# Pr_tica-11.net
KiCad netlist of a schematic drawn in EasyEDA
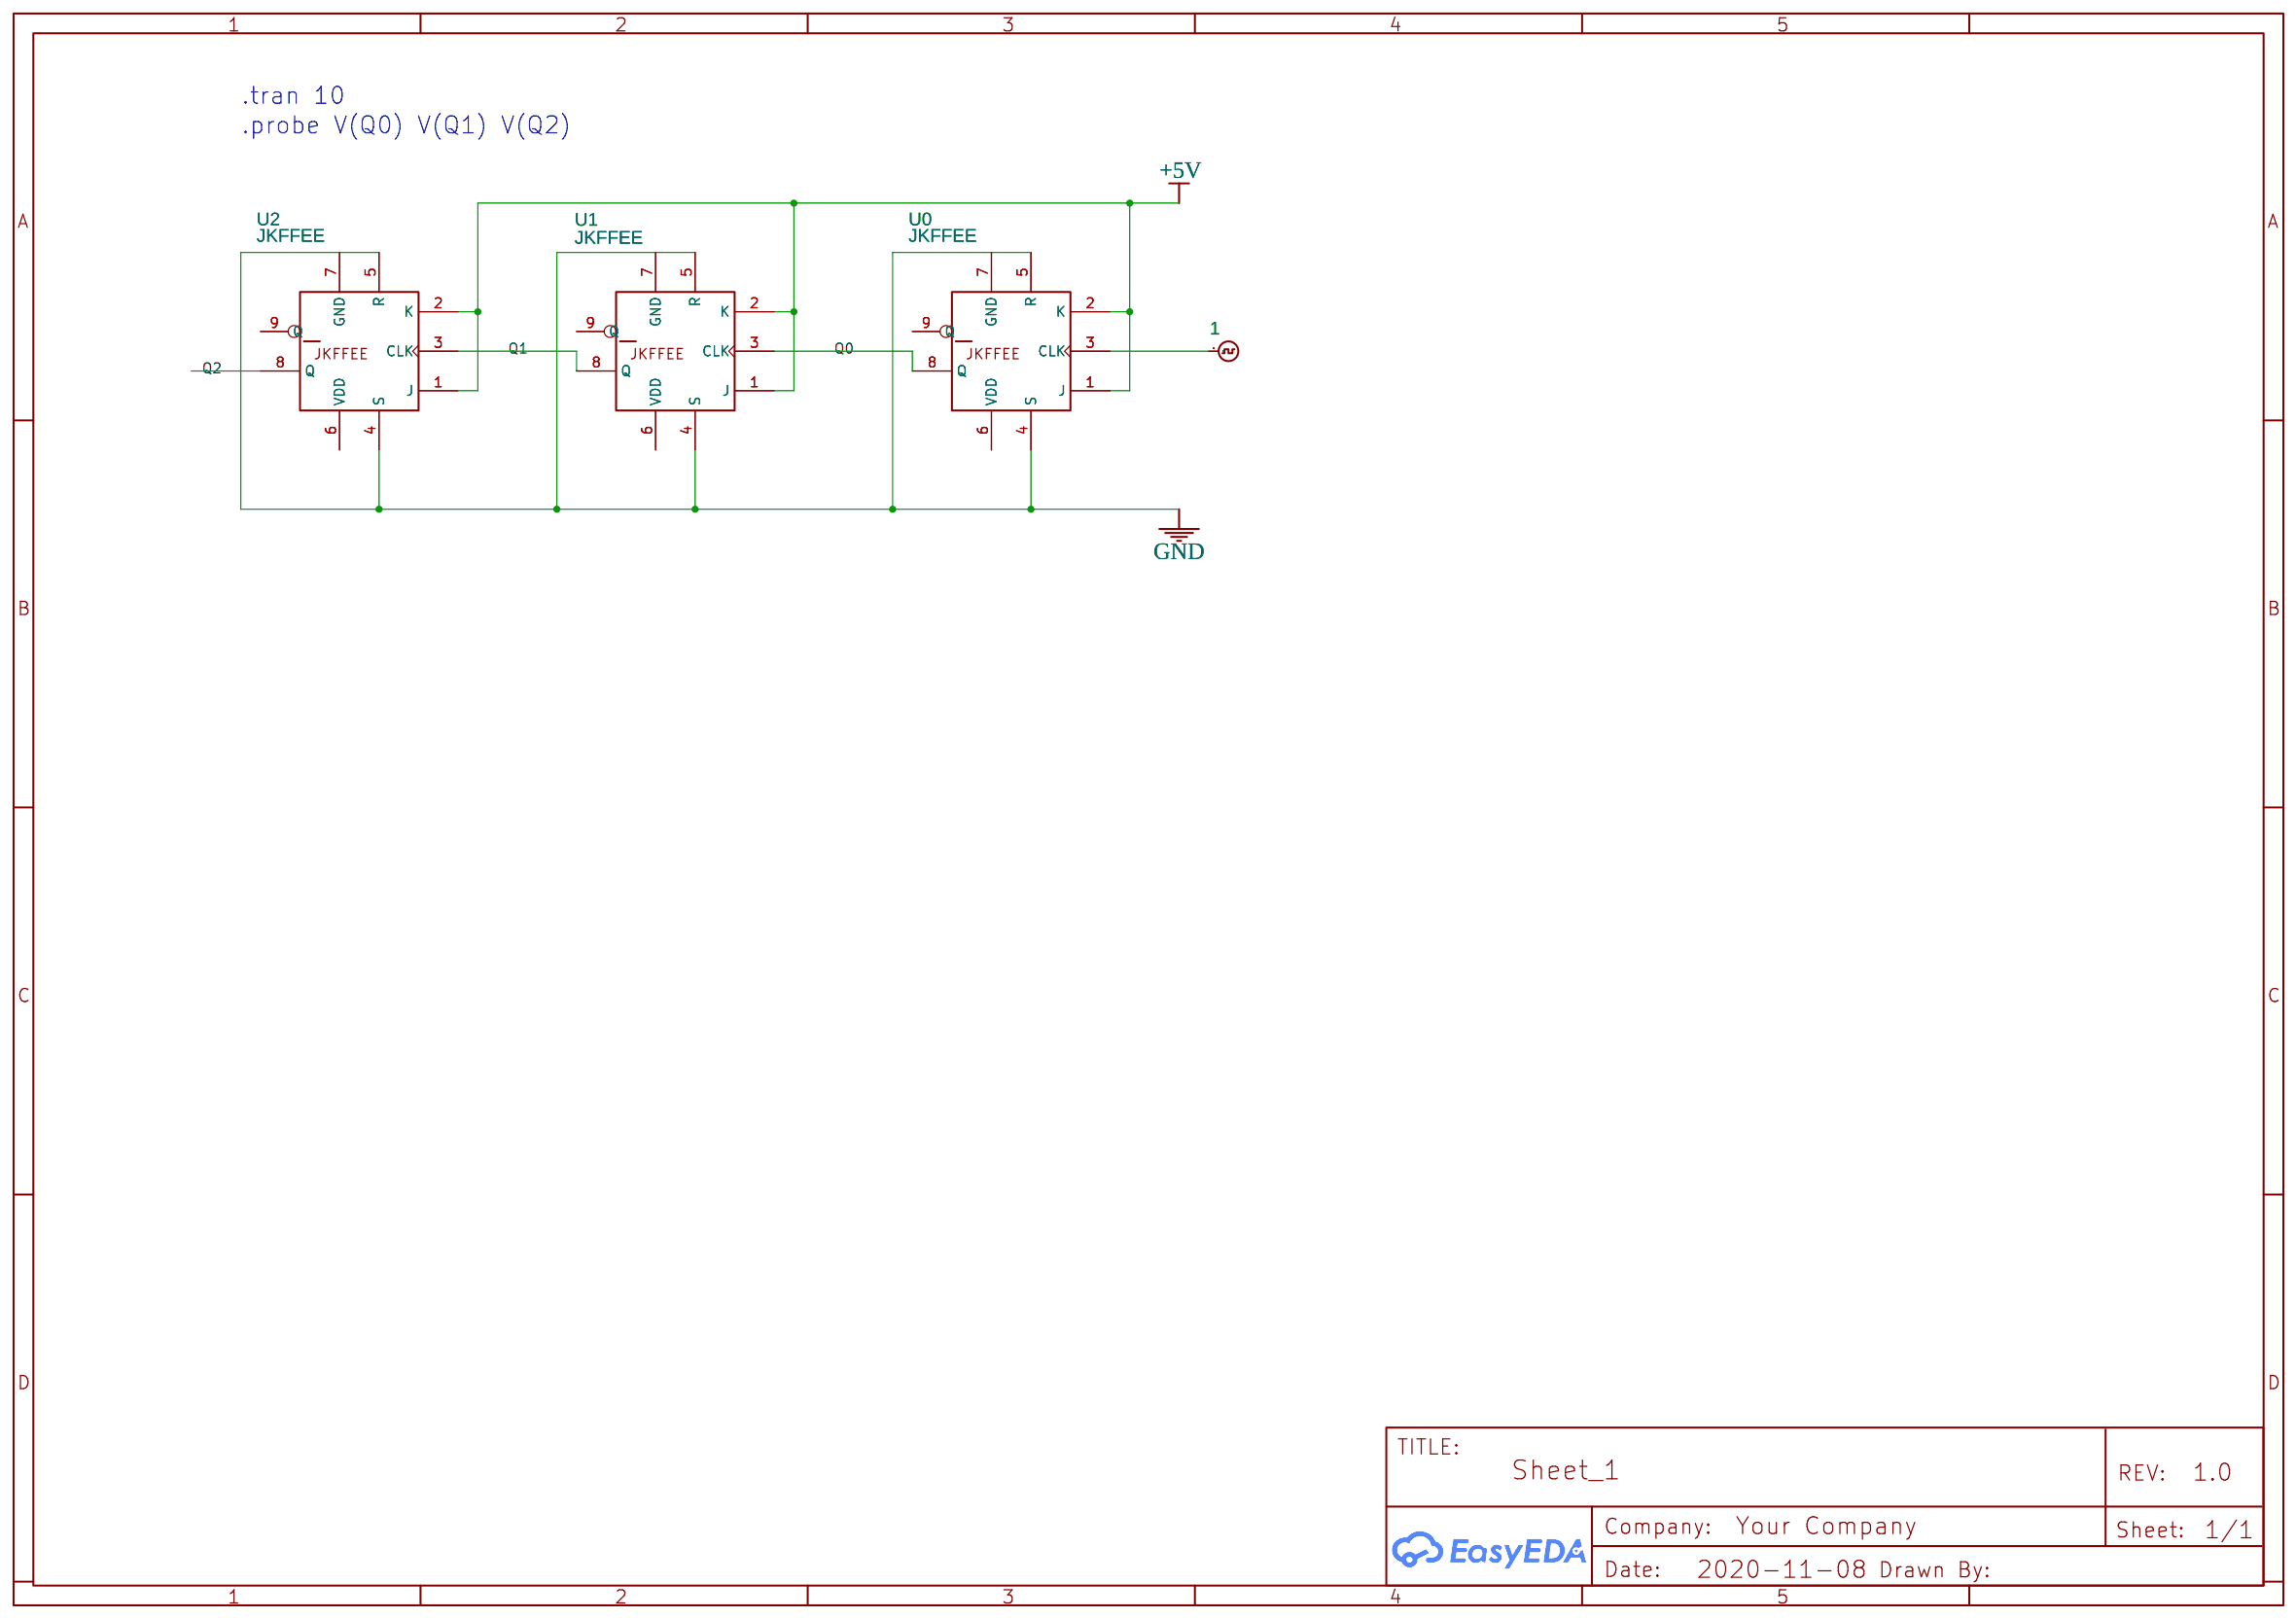
[diagram p0: schematic sheet]

(export (version "E")
  (design (tool "Eeschema 10.0.6"))
  (components
    (comp (ref "U0") (value "JKFFEE") (libsource (lib "") (part "LOGIC")))
    (comp (ref "U1") (value "JKFFEE") (libsource (lib "") (part "LOGIC")))
    (comp (ref "U2") (value "JKFFEE") (libsource (lib "") (part "LOGIC")))
    (comp (ref "U3") (value "1") (libsource (lib "") (part "DIGITALCLOCK")))
  )
  (nets
    (net (code "1") (name "+5V") (class "Default")
      (node (ref "U0") (pin "1") (pinfunction "J_1") (pintype "unspecified"))
      (node (ref "U0") (pin "2") (pinfunction "K_2") (pintype "unspecified"))
      (node (ref "U1") (pin "1") (pinfunction "J_1") (pintype "unspecified"))
      (node (ref "U1") (pin "2") (pinfunction "K_2") (pintype "unspecified"))
      (node (ref "U2") (pin "1") (pinfunction "J_1") (pintype "unspecified"))
      (node (ref "U2") (pin "2") (pinfunction "K_2") (pintype "unspecified"))
    )
    (net (code "2") (name "/Q0") (class "Default")
      (node (ref "U0") (pin "8") (pinfunction "Q_8") (pintype "unspecified"))
      (node (ref "U1") (pin "3") (pinfunction "CLK_3") (pintype "unspecified"))
    )
    (net (code "3") (name "/Q1") (class "Default")
      (node (ref "U1") (pin "8") (pinfunction "Q_8") (pintype "unspecified"))
      (node (ref "U2") (pin "3") (pinfunction "CLK_3") (pintype "unspecified"))
    )
    (net (code "4") (name "/Q2") (class "Default")
      (node (ref "U2") (pin "8") (pinfunction "Q_8") (pintype "unspecified"))
    )
    (net (code "5") (name "GND") (class "Default")
      (node (ref "U0") (pin "4") (pinfunction "S_4") (pintype "unspecified"))
      (node (ref "U0") (pin "5") (pinfunction "R_5") (pintype "unspecified"))
      (node (ref "U1") (pin "4") (pinfunction "S_4") (pintype "unspecified"))
      (node (ref "U1") (pin "5") (pinfunction "R_5") (pintype "unspecified"))
      (node (ref "U2") (pin "4") (pinfunction "S_4") (pintype "unspecified"))
      (node (ref "U2") (pin "5") (pinfunction "R_5") (pintype "unspecified"))
    )
    (net (code "6") (name "Net-(U0-CLK)") (class "Default")
      (node (ref "U0") (pin "3") (pinfunction "CLK_3") (pintype "unspecified"))
      (node (ref "U3") (pin "1") (pinfunction "1_1") (pintype "unspecified"))
    )
    (net (code "7") (name "unconnected-(U0-GND-Pad7)") (class "Default")
      (node (ref "U0") (pin "7") (pinfunction "GND_7") (pintype "unspecified"))
    )
    (net (code "8") (name "unconnected-(U0-Q-Pad9)") (class "Default")
      (node (ref "U0") (pin "9") (pinfunction "Q_9") (pintype "unspecified"))
    )
    (net (code "9") (name "unconnected-(U0-VDD-Pad6)") (class "Default")
      (node (ref "U0") (pin "6") (pinfunction "VDD_6") (pintype "unspecified"))
    )
    (net (code "10") (name "unconnected-(U1-GND-Pad7)") (class "Default")
      (node (ref "U1") (pin "7") (pinfunction "GND_7") (pintype "unspecified"))
    )
    (net (code "11") (name "unconnected-(U1-Q-Pad9)") (class "Default")
      (node (ref "U1") (pin "9") (pinfunction "Q_9") (pintype "unspecified"))
    )
    (net (code "12") (name "unconnected-(U1-VDD-Pad6)") (class "Default")
      (node (ref "U1") (pin "6") (pinfunction "VDD_6") (pintype "unspecified"))
    )
    (net (code "13") (name "unconnected-(U2-GND-Pad7)") (class "Default")
      (node (ref "U2") (pin "7") (pinfunction "GND_7") (pintype "unspecified"))
    )
    (net (code "14") (name "unconnected-(U2-Q-Pad9)") (class "Default")
      (node (ref "U2") (pin "9") (pinfunction "Q_9") (pintype "unspecified"))
    )
    (net (code "15") (name "unconnected-(U2-VDD-Pad6)") (class "Default")
      (node (ref "U2") (pin "6") (pinfunction "VDD_6") (pintype "unspecified"))
    )
  )
)
